# PCR_display_board.net
KiCad netlist of a schematic drawn in EAGLE
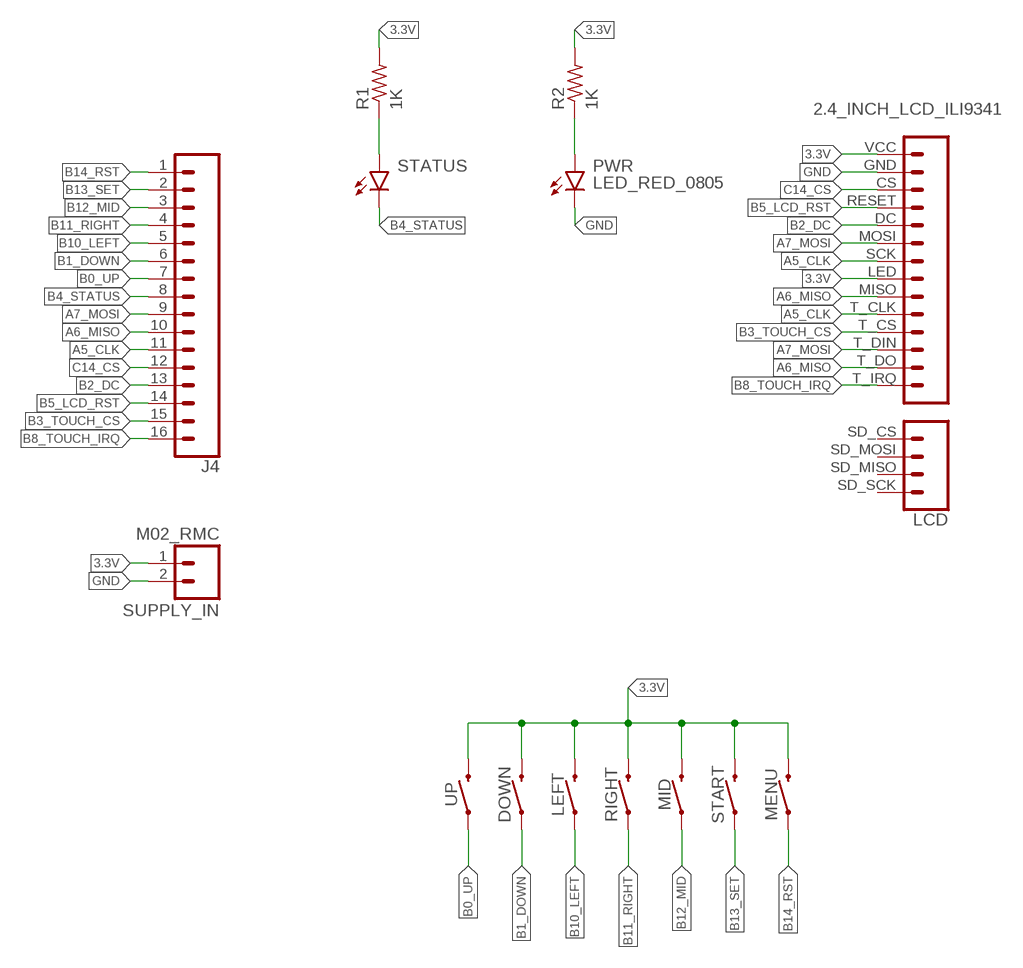
[diagram p0: schematic, sheet 1]

(export (version "E")
  (design (tool "Eeschema 10.0.6"))
  (components
    (comp (ref "DOWN")
      (value "PUSH_SWITCH_MOM")
      (footprint "eagle-import:HDRRAR4W64P254_2X2_1016X736X556B")
      (libsource (lib "eagle-import") (part "PUSH_SWITCH_MOM"))
    )
    (comp (ref "J4")
      (value "CONN_16")
      (footprint "eagle-import:1X16")
      (libsource (lib "eagle-import") (part "CONN_16"))
    )
    (comp (ref "LCD")
      (value "2.4_INCH_LCD_ILI9341")
      (footprint "eagle-import:XTAL1150X490X450N")
      (libsource (lib "eagle-import") (part "2.4_INCH_LCD_ILI9341"))
    )
    (comp (ref "LEFT")
      (value "PUSH_SWITCH_MOM")
      (footprint "eagle-import:HDRRAR4W64P254_2X2_1016X736X556B")
      (libsource (lib "eagle-import") (part "PUSH_SWITCH_MOM"))
    )
    (comp (ref "MENU")
      (value "PUSH_SWITCH_MOM")
      (footprint "eagle-import:HDRRAR4W64P254_2X2_1016X736X556B")
      (libsource (lib "eagle-import") (part "PUSH_SWITCH_MOM"))
    )
    (comp (ref "MID")
      (value "PUSH_SWITCH_MOM")
      (footprint "eagle-import:HDRRAR4W64P254_2X2_1016X736X556B")
      (libsource (lib "eagle-import") (part "PUSH_SWITCH_MOM"))
    )
    (comp (ref "PWR")
      (value "LED_RED_0805")
      (footprint "eagle-import:LED3MM")
      (libsource (lib "eagle-import") (part "LED3MM"))
    )
    (comp (ref "R1")
      (value "1K")
      (footprint "eagle-import:R0805")
      (libsource (lib "eagle-import") (part "R-US_R0805"))
    )
    (comp (ref "R2")
      (value "1K")
      (footprint "eagle-import:R0805")
      (libsource (lib "eagle-import") (part "R-US_R0805"))
    )
    (comp (ref "RIGHT")
      (value "PUSH_SWITCH_MOM")
      (footprint "eagle-import:HDRRAR4W64P254_2X2_1016X736X556B")
      (libsource (lib "eagle-import") (part "PUSH_SWITCH_MOM"))
    )
    (comp (ref "START")
      (value "PUSH_SWITCH_MOM")
      (footprint "eagle-import:HDRRAR4W64P254_2X2_1016X736X556B")
      (libsource (lib "eagle-import") (part "PUSH_SWITCH_MOM"))
    )
    (comp (ref "STATUS")
      (value "LED3MM")
      (footprint "eagle-import:LED3MM")
      (libsource (lib "eagle-import") (part "LED3MM"))
    )
    (comp (ref "SUPPLY_IN")
      (value "M02_RMC")
      (footprint "eagle-import:M02_RMC")
      (libsource (lib "eagle-import") (part "M02_RMC"))
    )
    (comp (ref "UP")
      (value "PUSH_SWITCH_MOM")
      (footprint "eagle-import:HDRRAR4W64P254_2X2_1016X736X556B")
      (libsource (lib "eagle-import") (part "PUSH_SWITCH_MOM"))
    )
  )
  (nets
    (net (code "1") (name "3.3V") (class "Default")
      (node (ref "DOWN") (pin "4") (pinfunction "2_4") (pintype "passive"))
      (node (ref "LCD") (pin "LED") (pinfunction "LED_LED") (pintype "input"))
      (node (ref "LCD") (pin "VCC") (pinfunction "VCC_VCC") (pintype "power_in"))
      (node (ref "LEFT") (pin "4") (pinfunction "2_4") (pintype "passive"))
      (node (ref "MENU") (pin "4") (pinfunction "2_4") (pintype "passive"))
      (node (ref "MID") (pin "4") (pinfunction "2_4") (pintype "passive"))
      (node (ref "R1") (pin "2") (pinfunction "2_2") (pintype "passive"))
      (node (ref "R2") (pin "2") (pinfunction "2_2") (pintype "passive"))
      (node (ref "RIGHT") (pin "4") (pinfunction "2_4") (pintype "passive"))
      (node (ref "START") (pin "4") (pinfunction "2_4") (pintype "passive"))
      (node (ref "SUPPLY_IN") (pin "1") (pinfunction "1_1") (pintype "passive"))
      (node (ref "UP") (pin "4") (pinfunction "2_4") (pintype "passive"))
    )
    (net (code "2") (name "A5_CLK") (class "Default")
      (node (ref "J4") (pin "11") (pinfunction "11_11") (pintype "passive"))
      (node (ref "LCD") (pin "SCK") (pinfunction "SCK_SCK") (pintype "input"))
      (node (ref "LCD") (pin "T_CLK") (pinfunction "T_CLK_T_CLK") (pintype "input"))
    )
    (net (code "3") (name "A6_MISO") (class "Default")
      (node (ref "J4") (pin "10") (pinfunction "10_10") (pintype "passive"))
      (node (ref "LCD") (pin "MISO") (pinfunction "SDO(MISO)_MISO") (pintype "output"))
      (node (ref "LCD") (pin "T_DO") (pinfunction "T_D0_T_DO") (pintype "output"))
    )
    (net (code "4") (name "A7_MOSI") (class "Default")
      (node (ref "J4") (pin "9") (pinfunction "9_9") (pintype "passive"))
      (node (ref "LCD") (pin "MOSI") (pinfunction "SDI(MOSI)_MOSI") (pintype "input"))
      (node (ref "LCD") (pin "T_DIN") (pinfunction "T_DIN_T_DIN") (pintype "input"))
    )
    (net (code "5") (name "B0_UP") (class "Default")
      (node (ref "J4") (pin "7") (pinfunction "7_7") (pintype "passive"))
      (node (ref "UP") (pin "1") (pinfunction "1_1") (pintype "passive"))
    )
    (net (code "6") (name "B1_DOWN") (class "Default")
      (node (ref "DOWN") (pin "1") (pinfunction "1_1") (pintype "passive"))
      (node (ref "J4") (pin "6") (pinfunction "6_6") (pintype "passive"))
    )
    (net (code "7") (name "B2_DC") (class "Default")
      (node (ref "J4") (pin "13") (pinfunction "13_13") (pintype "passive"))
      (node (ref "LCD") (pin "DC") (pinfunction "DC_DC") (pintype "input"))
    )
    (net (code "8") (name "B3_TOUCH_CS") (class "Default")
      (node (ref "J4") (pin "15") (pinfunction "15_15") (pintype "passive"))
      (node (ref "LCD") (pin "T_CS") (pinfunction "T_CS_T_CS") (pintype "input"))
    )
    (net (code "9") (name "B4_STATUS") (class "Default")
      (node (ref "J4") (pin "8") (pinfunction "8_8") (pintype "passive"))
      (node (ref "STATUS") (pin "K") (pinfunction "C_K") (pintype "passive"))
    )
    (net (code "10") (name "B5_LCD_RST") (class "Default")
      (node (ref "J4") (pin "14") (pinfunction "14_14") (pintype "passive"))
      (node (ref "LCD") (pin "RESET") (pinfunction "RESET_RESET") (pintype "input"))
    )
    (net (code "11") (name "B8_TOUCH_IRQ") (class "Default")
      (node (ref "J4") (pin "16") (pinfunction "16_16") (pintype "passive"))
      (node (ref "LCD") (pin "T_IRQ") (pinfunction "T_IRQ_T_IRQ") (pintype "passive"))
    )
    (net (code "12") (name "B10_LEFT") (class "Default")
      (node (ref "J4") (pin "5") (pinfunction "5_5") (pintype "passive"))
      (node (ref "LEFT") (pin "1") (pinfunction "1_1") (pintype "passive"))
    )
    (net (code "13") (name "B11_RIGHT") (class "Default")
      (node (ref "J4") (pin "4") (pinfunction "4_4") (pintype "passive"))
      (node (ref "RIGHT") (pin "1") (pinfunction "1_1") (pintype "passive"))
    )
    (net (code "14") (name "B12_MID") (class "Default")
      (node (ref "J4") (pin "3") (pinfunction "3_3") (pintype "passive"))
      (node (ref "MID") (pin "1") (pinfunction "1_1") (pintype "passive"))
    )
    (net (code "15") (name "B13_SET") (class "Default")
      (node (ref "J4") (pin "2") (pinfunction "2_2") (pintype "passive"))
      (node (ref "START") (pin "1") (pinfunction "1_1") (pintype "passive"))
    )
    (net (code "16") (name "B14_RST") (class "Default")
      (node (ref "J4") (pin "1") (pinfunction "1_1") (pintype "passive"))
      (node (ref "MENU") (pin "1") (pinfunction "1_1") (pintype "passive"))
    )
    (net (code "17") (name "C14_CS") (class "Default")
      (node (ref "J4") (pin "12") (pinfunction "12_12") (pintype "passive"))
      (node (ref "LCD") (pin "CS") (pinfunction "CS_CS") (pintype "input"))
    )
    (net (code "18") (name "GND") (class "Default")
      (node (ref "LCD") (pin "GND") (pinfunction "GND_GND") (pintype "power_in"))
      (node (ref "PWR") (pin "K") (pinfunction "C_K") (pintype "passive"))
      (node (ref "SUPPLY_IN") (pin "2") (pinfunction "2_2") (pintype "passive"))
    )
    (net (code "19") (name "Net-(PWR-PadA)") (class "Default")
      (node (ref "PWR") (pin "A") (pinfunction "A_A") (pintype "passive"))
      (node (ref "R2") (pin "1") (pinfunction "1_1") (pintype "passive"))
    )
    (net (code "20") (name "Net-(R1-Pad1)") (class "Default")
      (node (ref "R1") (pin "1") (pinfunction "1_1") (pintype "passive"))
      (node (ref "STATUS") (pin "A") (pinfunction "A_A") (pintype "passive"))
    )
    (net (code "21") (name "unconnected-(LCD-PadSD_CS)") (class "Default")
      (node (ref "LCD") (pin "SD_CS") (pinfunction "SD_CS_SD_CS") (pintype "input"))
    )
    (net (code "22") (name "unconnected-(LCD-PadSD_MISO)") (class "Default")
      (node (ref "LCD") (pin "SD_MISO") (pinfunction "SD_MISO_SD_MISO") (pintype "output"))
    )
    (net (code "23") (name "unconnected-(LCD-PadSD_MOSI)") (class "Default")
      (node (ref "LCD") (pin "SD_MOSI") (pinfunction "SD_MOSI_SD_MOSI") (pintype "input"))
    )
    (net (code "24") (name "unconnected-(LCD-PadSD_SCK)") (class "Default")
      (node (ref "LCD") (pin "SD_SCK") (pinfunction "SD_SCK_SD_SCK") (pintype "input"))
    )
  )
)
